# Diff_PressureSensor_SDP_v1_1_mrt2022.net
KiCad netlist of a schematic drawn in EAGLE
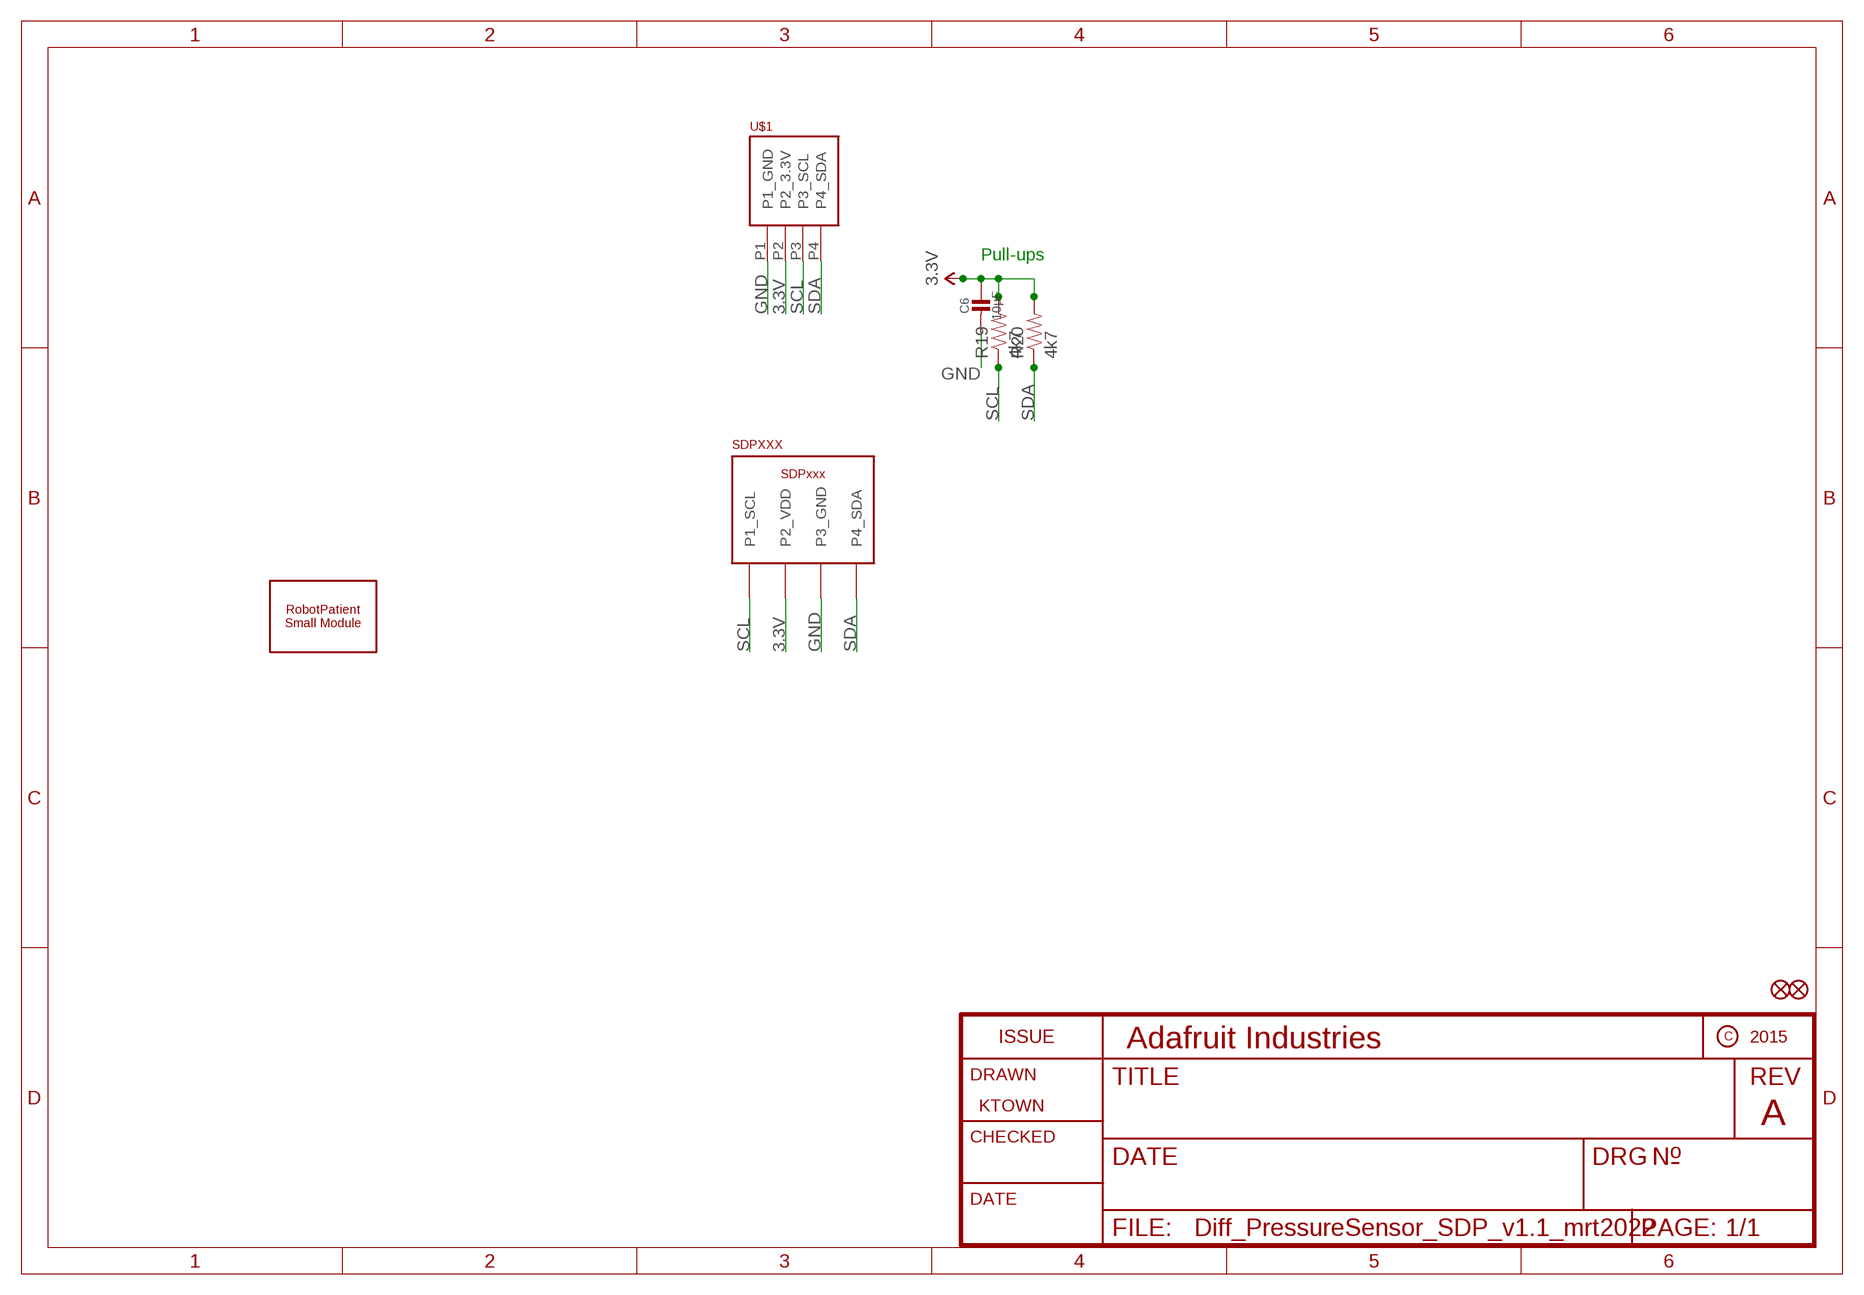
[diagram p0: schematic, sheet 1]

(export (version "E")
  (design (tool "Eeschema 10.0.6"))
  (components
    (comp (ref "C6")
      (value "10µF")
      (footprint "eagle-import:0805-NO")
      (libsource (lib "eagle-import") (part "CAP_CERAMIC0805-NOOUTLINE"))
    )
    (comp (ref "FID1")
      (value "FIDUCIAL\"\"")
      (footprint "eagle-import:FIDUCIAL_1MM")
      (libsource (lib "eagle-import") (part "FIDUCIAL{dblquote}{dblquote}"))
    )
    (comp (ref "FID2")
      (value "FIDUCIAL\"\"")
      (footprint "eagle-import:FIDUCIAL_1MM")
      (libsource (lib "eagle-import") (part "FIDUCIAL{dblquote}{dblquote}"))
    )
    (comp (ref "R19")
      (value "4k7")
      (footprint "eagle-import:0603-RES")
      (libsource (lib "eagle-import") (part "47KOHM1/10W1%(0603)"))
    )
    (comp (ref "R20")
      (value "4k7")
      (footprint "eagle-import:0603-RES")
      (libsource (lib "eagle-import") (part "47KOHM1/10W1%(0603)"))
    )
    (comp (ref "SDP810")
      (value "SDPXXX")
      (footprint "eagle-import:SDPXXX")
      (libsource (lib "eagle-import") (part "SDPXXX"))
    )
    (comp (ref "U$1")
      (value "PHOENIX_PTSM_M4_THANGLE")
      (footprint "eagle-import:PTSM_M4_TH")
      (libsource (lib "eagle-import") (part "PHOENIX_PTSM_M4_THANGLE"))
    )
    (comp (ref "U$2")
      (value "ROBOTPATIENT_SMALL_MODULEBOARD")
      (footprint "eagle-import:RP_SMALL_SENSOR_OUTLINE")
      (libsource (lib "eagle-import") (part "ROBOTPATIENT_SMALL_MODULEBOARD"))
    )
  )
  (nets
    (net (code "1") (name "/GND") (class "Default")
      (node (ref "C6") (pin "2") (pinfunction "2_2") (pintype "passive"))
      (node (ref "SDP810") (pin "P2_GND") (pinfunction "P3_GND_P2_GND") (pintype "bidirectional"))
      (node (ref "U$1") (pin "P1") (pinfunction "P1_GND_P1") (pintype "power_in"))
    )
    (net (code "2") (name "/SCL") (class "Default")
      (node (ref "R19") (pin "1") (pinfunction "1_1") (pintype "passive"))
      (node (ref "SDP810") (pin "P4_CLK") (pinfunction "P1_SCL_P4_CLK") (pintype "bidirectional"))
      (node (ref "U$1") (pin "P3") (pinfunction "P3_SCL_P3") (pintype "bidirectional"))
    )
    (net (code "3") (name "/SDA") (class "Default")
      (node (ref "R20") (pin "1") (pinfunction "1_1") (pintype "passive"))
      (node (ref "SDP810") (pin "P1_SDA") (pinfunction "P4_SDA_P1_SDA") (pintype "bidirectional"))
      (node (ref "U$1") (pin "P4") (pinfunction "P4_SDA_P4") (pintype "bidirectional"))
    )
    (net (code "4") (name "3.3V") (class "Default")
      (node (ref "C6") (pin "1") (pinfunction "1_1") (pintype "passive"))
      (node (ref "R19") (pin "2") (pinfunction "2_2") (pintype "passive"))
      (node (ref "R20") (pin "2") (pinfunction "2_2") (pintype "passive"))
      (node (ref "SDP810") (pin "P3_VCC") (pinfunction "P2_VDD_P3_VCC") (pintype "bidirectional"))
      (node (ref "U$1") (pin "P2") (pinfunction "P2_3.3V_P2") (pintype "power_in"))
    )
  )
)
